# Sheet1.net
KiCad netlist of a schematic drawn in Altium Designer
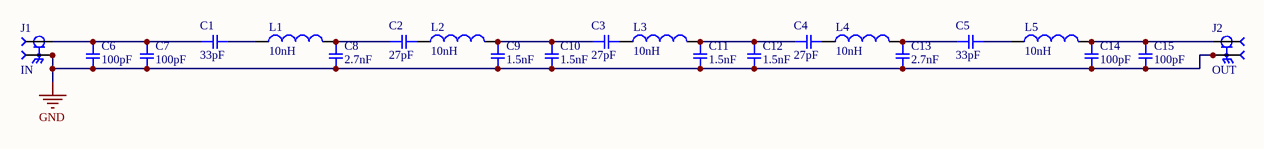
[diagram p0: Sheet1.SchDoc]

(export (version "E")
  (design (tool "Eeschema 10.0.6"))
  (components
    (comp (ref "C1")
      (value "33pF")
      (footprint "SMD-0402C")
      (description "CAP CER 33PF 50V NP0 0402")
      (fields
        (field (name "DIGI-KEY PART NUMBER") "490-11148-1-ND")
        (field (name "PART NUMBER") "GCM1555C1H330JA16D")
      )
      (libsource (lib "capacitor_murata_0402") (part "GCM1555C1H330JA16D"))
    )
    (comp (ref "C2")
      (value "27pF")
      (footprint "SMD-0402C")
      (description "CAP CER 27PF 50V NP0 0402")
      (fields
        (field (name "DIGI-KEY PART NUMBER") "490-12651-1-ND")
        (field (name "PART NUMBER") "GCM1555C1H270JA16D")
      )
      (libsource (lib "capacitor_murata_0402") (part "GCM1555C1H270JA16D"))
    )
    (comp (ref "C3")
      (value "27pF")
      (footprint "SMD-0402C")
      (description "CAP CER 27PF 50V NP0 0402")
      (fields
        (field (name "DIGI-KEY PART NUMBER") "490-12651-1-ND")
        (field (name "PART NUMBER") "GCM1555C1H270JA16D")
      )
      (libsource (lib "capacitor_murata_0402") (part "GCM1555C1H270JA16D"))
    )
    (comp (ref "C4")
      (value "27pF")
      (footprint "SMD-0402C")
      (description "CAP CER 27PF 50V NP0 0402")
      (fields
        (field (name "DIGI-KEY PART NUMBER") "490-12651-1-ND")
        (field (name "PART NUMBER") "GCM1555C1H270JA16D")
      )
      (libsource (lib "capacitor_murata_0402") (part "GCM1555C1H270JA16D"))
    )
    (comp (ref "C5")
      (value "33pF")
      (footprint "SMD-0402C")
      (description "CAP CER 33PF 50V NP0 0402")
      (fields
        (field (name "DIGI-KEY PART NUMBER") "490-11148-1-ND")
        (field (name "PART NUMBER") "GCM1555C1H330JA16D")
      )
      (libsource (lib "capacitor_murata_0402") (part "GCM1555C1H330JA16D"))
    )
    (comp (ref "C6")
      (value "100pF")
      (footprint "SMD-0402C")
      (description "CAP CER 100PF 50V NP0 0402")
      (fields
        (field (name "DIGI-KEY PART NUMBER") "490-10669-1-ND")
        (field (name "PART NUMBER") "GCM1555C1H101JA16D")
      )
      (libsource (lib "capacitor_murata_0402") (part "GCM1555C1H101JA16D"))
    )
    (comp (ref "C7")
      (value "100pF")
      (footprint "SMD-0402C")
      (description "CAP CER 100PF 50V NP0 0402")
      (fields
        (field (name "DIGI-KEY PART NUMBER") "490-10669-1-ND")
        (field (name "PART NUMBER") "GCM1555C1H101JA16D")
      )
      (libsource (lib "capacitor_murata_0402") (part "GCM1555C1H101JA16D"))
    )
    (comp (ref "C8")
      (value "2.7nF")
      (footprint "SMD-0402C")
      (description "CAP CER 2700PF 10V U2J 0402")
      (fields
        (field (name "DIGI-KEY PART NUMBER") "490-6275-1-ND")
        (field (name "PART NUMBER") "GRM1557U1A272JA01D")
      )
      (libsource (lib "capacitor_murata_0402") (part "GRM1557U1A272JA01D"))
    )
    (comp (ref "C9")
      (value "1.5nF")
      (footprint "SMD-0402C")
      (description "CAP CER 1500PF 50V X7R 0402")
      (fields
        (field (name "DIGI-KEY PART NUMBER") "490-8000-1-ND")
        (field (name "PART NUMBER") "GCM155R71H152KA37D")
      )
      (libsource (lib "capacitor_murata_0402") (part "GCM155R71H152KA37D"))
    )
    (comp (ref "C10")
      (value "1.5nF")
      (footprint "SMD-0402C")
      (description "CAP CER 1500PF 50V X7R 0402")
      (fields
        (field (name "DIGI-KEY PART NUMBER") "490-8000-1-ND")
        (field (name "PART NUMBER") "GCM155R71H152KA37D")
      )
      (libsource (lib "capacitor_murata_0402") (part "GCM155R71H152KA37D"))
    )
    (comp (ref "C11")
      (value "1.5nF")
      (footprint "SMD-0402C")
      (description "CAP CER 1500PF 50V X7R 0402")
      (fields
        (field (name "DIGI-KEY PART NUMBER") "490-8000-1-ND")
        (field (name "PART NUMBER") "GCM155R71H152KA37D")
      )
      (libsource (lib "capacitor_murata_0402") (part "GCM155R71H152KA37D"))
    )
    (comp (ref "C12")
      (value "1.5nF")
      (footprint "SMD-0402C")
      (description "CAP CER 1500PF 50V X7R 0402")
      (fields
        (field (name "DIGI-KEY PART NUMBER") "490-8000-1-ND")
        (field (name "PART NUMBER") "GCM155R71H152KA37D")
      )
      (libsource (lib "capacitor_murata_0402") (part "GCM155R71H152KA37D"))
    )
    (comp (ref "C13")
      (value "2.7nF")
      (footprint "SMD-0402C")
      (description "CAP CER 2700PF 10V U2J 0402")
      (fields
        (field (name "DIGI-KEY PART NUMBER") "490-6275-1-ND")
        (field (name "PART NUMBER") "GRM1557U1A272JA01D")
      )
      (libsource (lib "capacitor_murata_0402") (part "GRM1557U1A272JA01D"))
    )
    (comp (ref "C14")
      (value "100pF")
      (footprint "SMD-0402C")
      (description "CAP CER 100PF 50V NP0 0402")
      (fields
        (field (name "DIGI-KEY PART NUMBER") "490-10669-1-ND")
        (field (name "PART NUMBER") "GCM1555C1H101JA16D")
      )
      (libsource (lib "capacitor_murata_0402") (part "GCM1555C1H101JA16D"))
    )
    (comp (ref "C15")
      (value "100pF")
      (footprint "SMD-0402C")
      (description "CAP CER 100PF 50V NP0 0402")
      (fields
        (field (name "DIGI-KEY PART NUMBER") "490-10669-1-ND")
        (field (name "PART NUMBER") "GCM1555C1H101JA16D")
      )
      (libsource (lib "capacitor_murata_0402") (part "GCM1555C1H101JA16D"))
    )
    (comp (ref "J1")
      (value "IN")
      (footprint "LPRS_SMACONNECTOR")
      (description "SMA female RF coaxial connector for SMA male RF antennas.")
      (fields (field (name "MP") "SMACONNECTOR"))
      (libsource (lib "SMACONNECTOR") (part "SMACONNECTOR"))
    )
    (comp (ref "J2")
      (value "OUT")
      (footprint "LPRS_SMACONNECTOR")
      (description "SMA female RF coaxial connector for SMA male RF antennas.")
      (fields (field (name "MP") "SMACONNECTOR"))
      (libsource (lib "SMACONNECTOR") (part "SMACONNECTOR"))
    )
    (comp (ref "L1")
      (value "10nH")
      (footprint "0402-A")
      (fields (field (name "PUBLISHER") "Altium Limited"))
      (libsource (lib "Miscellaneous Devices") (part "Inductor"))
    )
    (comp (ref "L2")
      (value "10nH")
      (footprint "0402-A")
      (fields (field (name "PUBLISHER") "Altium Limited"))
      (libsource (lib "Miscellaneous Devices") (part "Inductor"))
    )
    (comp (ref "L3")
      (value "10nH")
      (footprint "0402-A")
      (fields (field (name "PUBLISHER") "Altium Limited"))
      (libsource (lib "Miscellaneous Devices") (part "Inductor"))
    )
    (comp (ref "L4")
      (value "10nH")
      (footprint "0402-A")
      (fields (field (name "PUBLISHER") "Altium Limited"))
      (libsource (lib "Miscellaneous Devices") (part "Inductor"))
    )
    (comp (ref "L5")
      (value "10nH")
      (footprint "0402-A")
      (fields (field (name "PUBLISHER") "Altium Limited"))
      (libsource (lib "Miscellaneous Devices") (part "Inductor"))
    )
  )
  (nets
    (net (code "1") (name "GND") (class "Default")
      (node (ref "C10") (pin "2") (pinfunction "2_2") (pintype "passive"))
      (node (ref "C11") (pin "2") (pinfunction "2_2") (pintype "passive"))
      (node (ref "C12") (pin "2") (pinfunction "2_2") (pintype "passive"))
      (node (ref "C13") (pin "2") (pinfunction "2_2") (pintype "passive"))
      (node (ref "C14") (pin "2") (pinfunction "2_2") (pintype "passive"))
      (node (ref "C15") (pin "2") (pinfunction "2_2") (pintype "passive"))
      (node (ref "C6") (pin "2") (pinfunction "2_2") (pintype "passive"))
      (node (ref "C7") (pin "2") (pinfunction "2_2") (pintype "passive"))
      (node (ref "C8") (pin "2") (pinfunction "2_2") (pintype "passive"))
      (node (ref "C9") (pin "2") (pinfunction "2_2") (pintype "passive"))
      (node (ref "J1") (pin "2") (pinfunction "2_2") (pintype "passive"))
      (node (ref "J1") (pin "3") (pinfunction "2_3") (pintype "passive"))
      (node (ref "J1") (pin "4") (pinfunction "2_4") (pintype "passive"))
      (node (ref "J1") (pin "5") (pinfunction "2_5") (pintype "passive"))
      (node (ref "J2") (pin "2") (pinfunction "2_2") (pintype "passive"))
      (node (ref "J2") (pin "3") (pinfunction "2_3") (pintype "passive"))
      (node (ref "J2") (pin "4") (pinfunction "2_4") (pintype "passive"))
      (node (ref "J2") (pin "5") (pinfunction "2_5") (pintype "passive"))
    )
    (net (code "2") (name "Net-(C1-Pad1)") (class "Default")
      (node (ref "C1") (pin "1") (pinfunction "1_1") (pintype "passive"))
      (node (ref "C6") (pin "1") (pinfunction "1_1") (pintype "passive"))
      (node (ref "C7") (pin "1") (pinfunction "1_1") (pintype "passive"))
      (node (ref "J1") (pin "1") (pinfunction "1_1") (pintype "passive"))
    )
    (net (code "3") (name "Net-(C1-Pad2)") (class "Default")
      (node (ref "C1") (pin "2") (pinfunction "2_2") (pintype "passive"))
      (node (ref "L1") (pin "1") (pinfunction "1_1") (pintype "passive"))
    )
    (net (code "4") (name "Net-(C2-Pad1)") (class "Default")
      (node (ref "C2") (pin "1") (pinfunction "1_1") (pintype "passive"))
      (node (ref "C8") (pin "1") (pinfunction "1_1") (pintype "passive"))
      (node (ref "L1") (pin "2") (pinfunction "2_2") (pintype "passive"))
    )
    (net (code "5") (name "Net-(C2-Pad2)") (class "Default")
      (node (ref "C2") (pin "2") (pinfunction "2_2") (pintype "passive"))
      (node (ref "L2") (pin "1") (pinfunction "1_1") (pintype "passive"))
    )
    (net (code "6") (name "Net-(C3-Pad2)") (class "Default")
      (node (ref "C3") (pin "2") (pinfunction "2_2") (pintype "passive"))
      (node (ref "L3") (pin "1") (pinfunction "1_1") (pintype "passive"))
    )
    (net (code "7") (name "Net-(C4-Pad2)") (class "Default")
      (node (ref "C4") (pin "2") (pinfunction "2_2") (pintype "passive"))
      (node (ref "L4") (pin "1") (pinfunction "1_1") (pintype "passive"))
    )
    (net (code "8") (name "Net-(C5-Pad2)") (class "Default")
      (node (ref "C5") (pin "2") (pinfunction "2_2") (pintype "passive"))
      (node (ref "L5") (pin "1") (pinfunction "1_1") (pintype "passive"))
    )
    (net (code "9") (name "Net-(C10-Pad1)") (class "Default")
      (node (ref "C10") (pin "1") (pinfunction "1_1") (pintype "passive"))
      (node (ref "C3") (pin "1") (pinfunction "1_1") (pintype "passive"))
      (node (ref "C9") (pin "1") (pinfunction "1_1") (pintype "passive"))
      (node (ref "L2") (pin "2") (pinfunction "2_2") (pintype "passive"))
    )
    (net (code "10") (name "Net-(C11-Pad1)") (class "Default")
      (node (ref "C11") (pin "1") (pinfunction "1_1") (pintype "passive"))
      (node (ref "C12") (pin "1") (pinfunction "1_1") (pintype "passive"))
      (node (ref "C4") (pin "1") (pinfunction "1_1") (pintype "passive"))
      (node (ref "L3") (pin "2") (pinfunction "2_2") (pintype "passive"))
    )
    (net (code "11") (name "Net-(C13-Pad1)") (class "Default")
      (node (ref "C13") (pin "1") (pinfunction "1_1") (pintype "passive"))
      (node (ref "C5") (pin "1") (pinfunction "1_1") (pintype "passive"))
      (node (ref "L4") (pin "2") (pinfunction "2_2") (pintype "passive"))
    )
    (net (code "12") (name "Net-(C14-Pad1)") (class "Default")
      (node (ref "C14") (pin "1") (pinfunction "1_1") (pintype "passive"))
      (node (ref "C15") (pin "1") (pinfunction "1_1") (pintype "passive"))
      (node (ref "J2") (pin "1") (pinfunction "1_1") (pintype "passive"))
      (node (ref "L5") (pin "2") (pinfunction "2_2") (pintype "passive"))
    )
  )
)
